# PCB_power-distribution.net
KiCad netlist of a schematic drawn in EasyEDA Pro
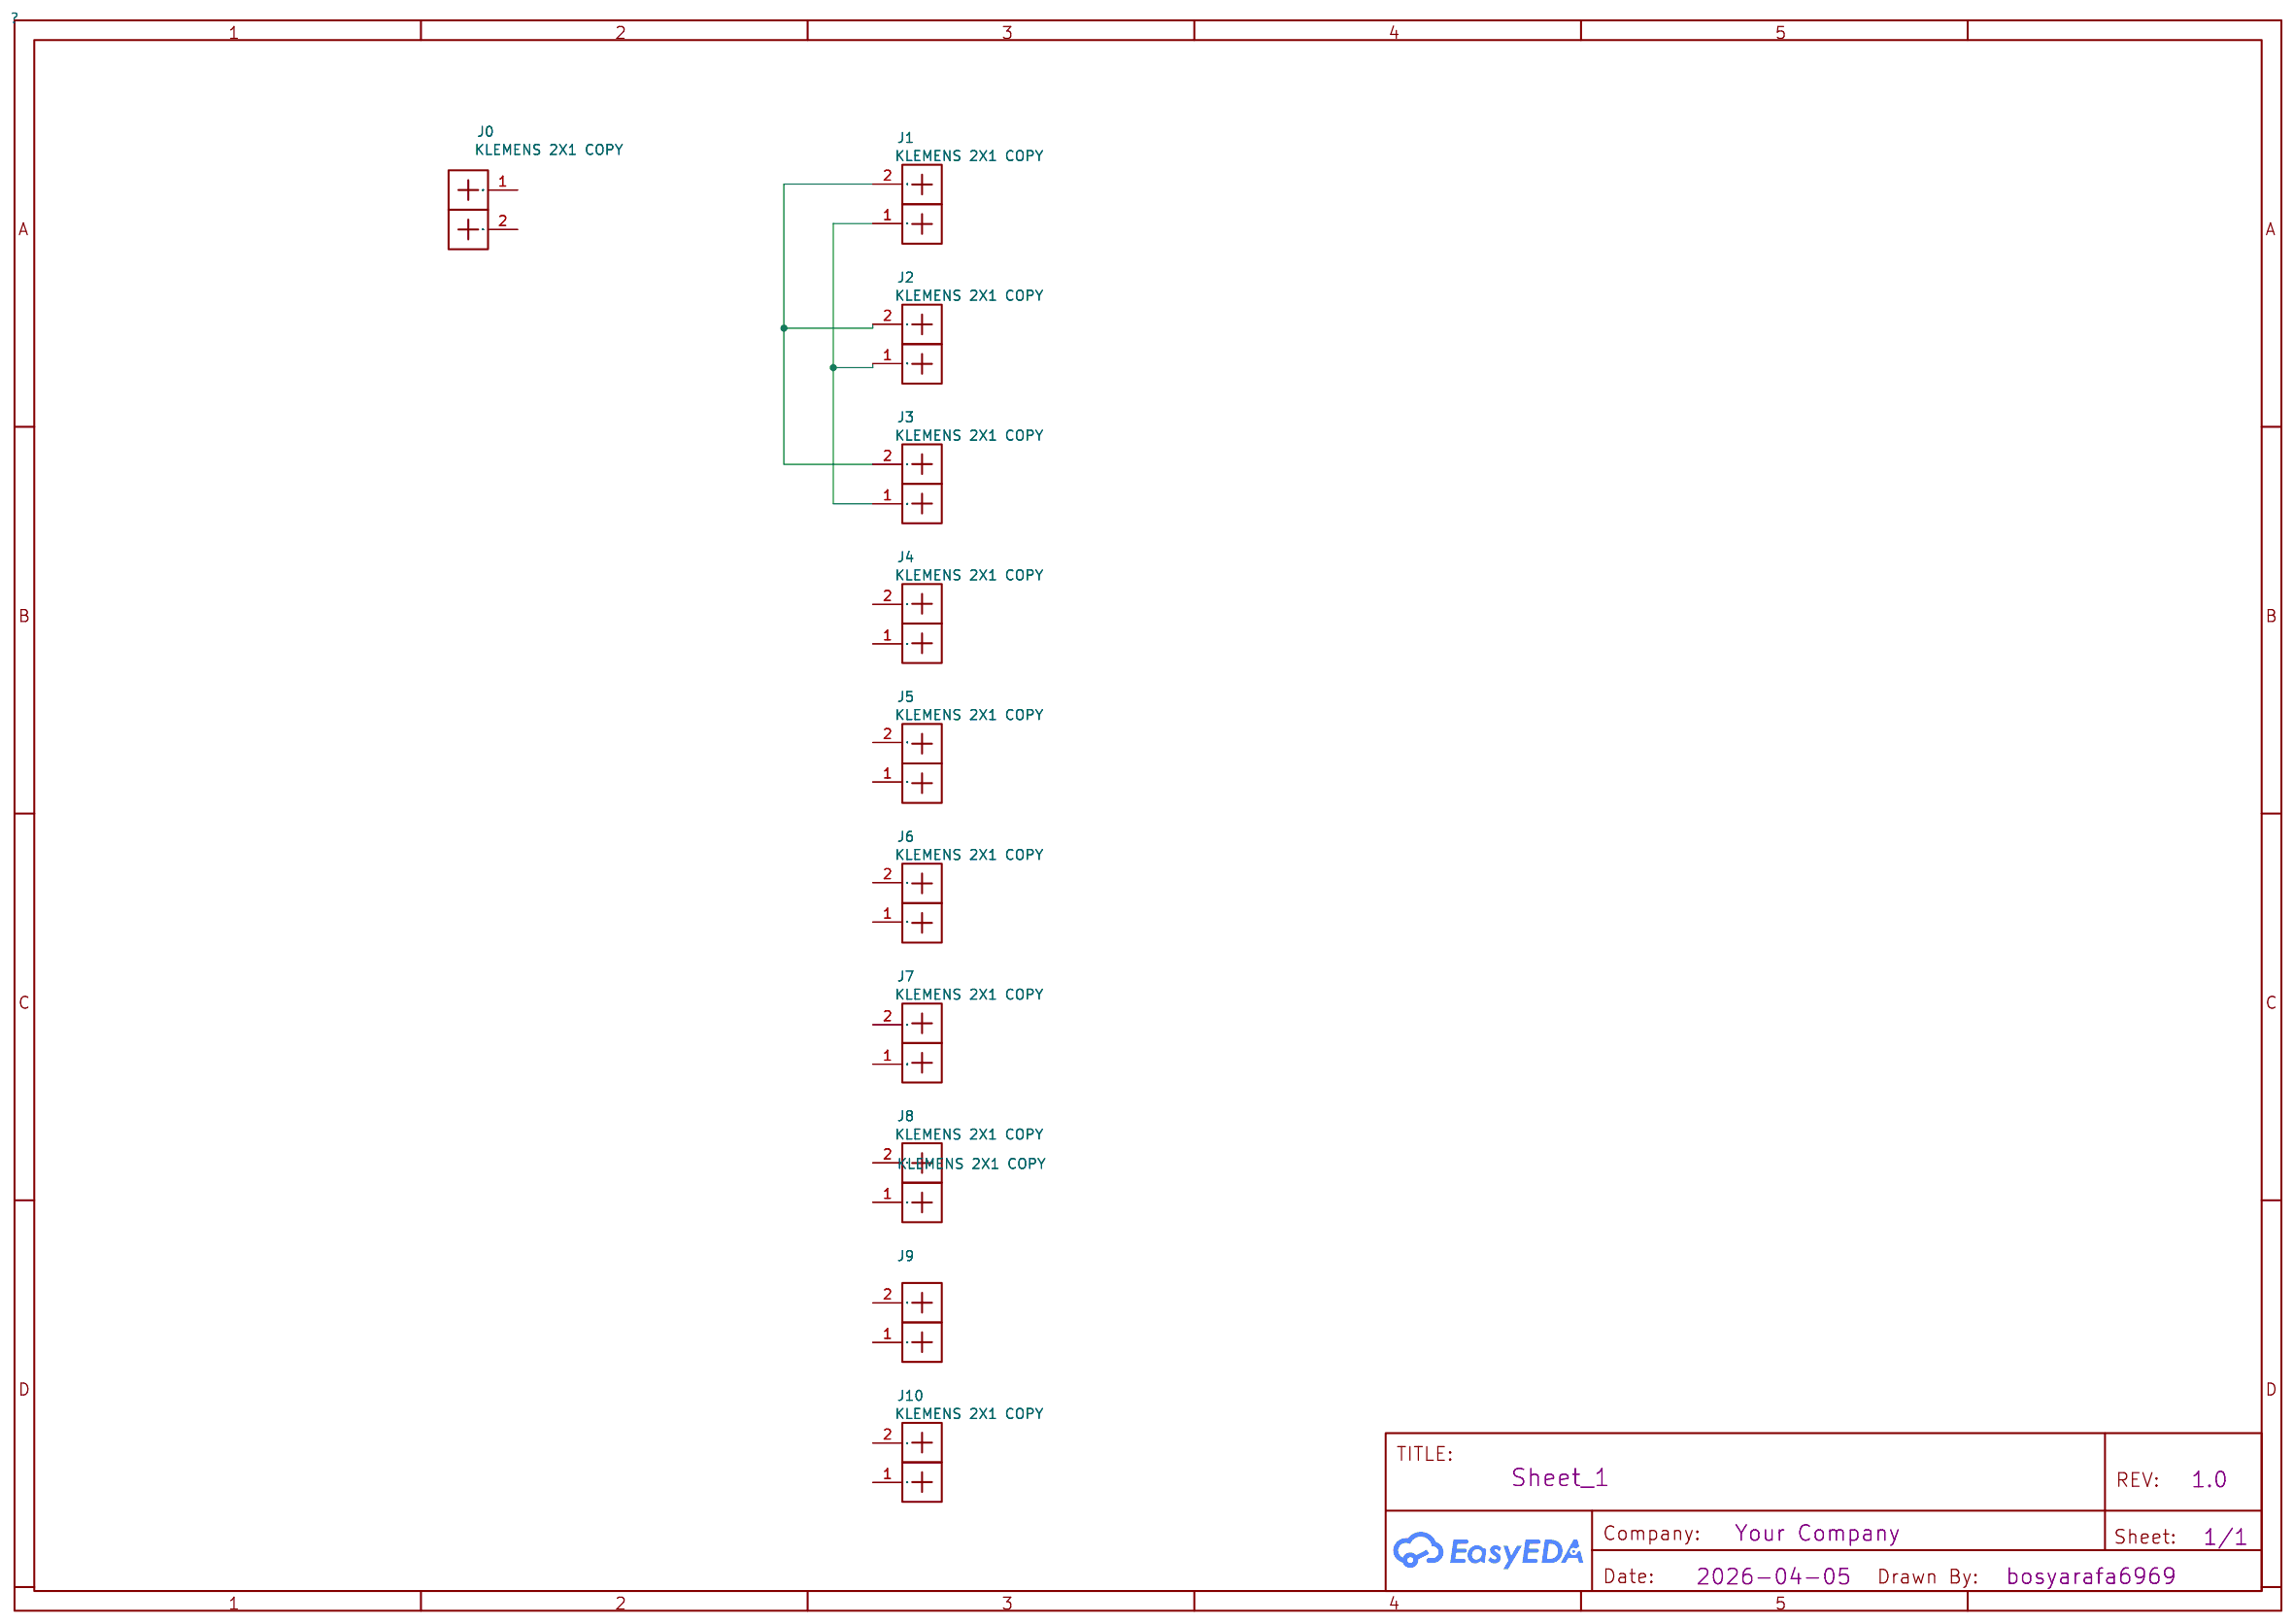
[diagram p0: schematic sheet]

(export (version "E")
  (design (tool "Eeschema 10.0.6"))
  (components
    (comp (ref "J0")
      (value "KLEMENS 2X1 COPY")
      (footprint "easyedapro:TERMINALBLOCK_METZCONNECT:TERMINALBLOCK_METZCONNECT_360271_1X01_HORIZONTAL_SCREWM3.0_BOXED")
      (fields
        (field (name "Comment") "Connector_Screw_Terminal_01x01")
        (field (name "Contributor") "fjju1212")
      )
      (libsource (lib "") (part "KLEMENS 2X1 COPY_3"))
    )
    (comp (ref "J1")
      (value "KLEMENS 2X1 COPY")
      (footprint "easyedapro:TERMINALBLOCK_METZCONNECT:TERMINALBLOCK_METZCONNECT_360271_1X01_HORIZONTAL_SCREWM3.0_BOXED")
      (fields
        (field (name "Comment") "Connector_Screw_Terminal_01x01")
        (field (name "Contributor") "fjju1212")
      )
      (libsource (lib "") (part "KLEMENS 2X1 COPY_6"))
    )
    (comp (ref "J2")
      (value "KLEMENS 2X1 COPY")
      (footprint "easyedapro:TERMINALBLOCK_METZCONNECT:TERMINALBLOCK_METZCONNECT_360271_1X01_HORIZONTAL_SCREWM3.0_BOXED")
      (fields
        (field (name "Comment") "Connector_Screw_Terminal_01x01")
        (field (name "Contributor") "fjju1212")
      )
      (libsource (lib "") (part "KLEMENS 2X1 COPY_1"))
    )
    (comp (ref "J3")
      (value "KLEMENS 2X1 COPY")
      (footprint "easyedapro:TERMINALBLOCK_METZCONNECT:TERMINALBLOCK_METZCONNECT_360271_1X01_HORIZONTAL_SCREWM3.0_BOXED")
      (fields
        (field (name "Comment") "Connector_Screw_Terminal_01x01")
        (field (name "Contributor") "fjju1212")
      )
      (libsource (lib "") (part "KLEMENS 2X1 COPY_7"))
    )
    (comp (ref "J4")
      (value "KLEMENS 2X1 COPY")
      (footprint "easyedapro:TERMINALBLOCK_METZCONNECT:TERMINALBLOCK_METZCONNECT_360271_1X01_HORIZONTAL_SCREWM3.0_BOXED")
      (fields
        (field (name "Comment") "Connector_Screw_Terminal_01x01")
        (field (name "Contributor") "fjju1212")
      )
      (libsource (lib "") (part "KLEMENS 2X1 COPY_8"))
    )
    (comp (ref "J5")
      (value "KLEMENS 2X1 COPY")
      (footprint "easyedapro:TERMINALBLOCK_METZCONNECT:TERMINALBLOCK_METZCONNECT_360271_1X01_HORIZONTAL_SCREWM3.0_BOXED")
      (fields
        (field (name "Comment") "Connector_Screw_Terminal_01x01")
        (field (name "Contributor") "fjju1212")
      )
      (libsource (lib "") (part "KLEMENS 2X1 COPY_5"))
    )
    (comp (ref "J6")
      (value "KLEMENS 2X1 COPY")
      (footprint "easyedapro:TERMINALBLOCK_METZCONNECT:TERMINALBLOCK_METZCONNECT_360271_1X01_HORIZONTAL_SCREWM3.0_BOXED")
      (fields
        (field (name "Comment") "Connector_Screw_Terminal_01x01")
        (field (name "Contributor") "fjju1212")
      )
      (libsource (lib "") (part "KLEMENS 2X1 COPY_2"))
    )
    (comp (ref "J7")
      (value "KLEMENS 2X1 COPY")
      (footprint "easyedapro:TERMINALBLOCK_METZCONNECT:TERMINALBLOCK_METZCONNECT_360271_1X01_HORIZONTAL_SCREWM3.0_BOXED")
      (fields
        (field (name "Comment") "Connector_Screw_Terminal_01x01")
        (field (name "Contributor") "fjju1212")
      )
      (libsource (lib "") (part "KLEMENS 2X1 COPY_4"))
    )
    (comp (ref "J8")
      (value "KLEMENS 2X1 COPY")
      (footprint "easyedapro:TERMINALBLOCK_METZCONNECT:TERMINALBLOCK_METZCONNECT_360271_1X01_HORIZONTAL_SCREWM3.0_BOXED")
      (fields
        (field (name "Comment") "Connector_Screw_Terminal_01x01")
        (field (name "Contributor") "fjju1212")
      )
      (libsource (lib "") (part "KLEMENS 2X1 COPY_1"))
    )
    (comp (ref "J9")
      (value "KLEMENS 2X1 COPY")
      (footprint "easyedapro:TERMINALBLOCK_METZCONNECT:TERMINALBLOCK_METZCONNECT_360271_1X01_HORIZONTAL_SCREWM3.0_BOXED")
      (fields
        (field (name "Comment") "Connector_Screw_Terminal_01x01")
        (field (name "Contributor") "fjju1212")
      )
      (libsource (lib "") (part "KLEMENS 2X1 COPY_7"))
    )
    (comp (ref "J10")
      (value "KLEMENS 2X1 COPY")
      (footprint "easyedapro:TERMINALBLOCK_METZCONNECT:TERMINALBLOCK_METZCONNECT_360271_1X01_HORIZONTAL_SCREWM3.0_BOXED")
      (fields
        (field (name "Comment") "Connector_Screw_Terminal_01x01")
        (field (name "Contributor") "fjju1212")
      )
      (libsource (lib "easyedapro") (part "KLEMENS 2X1 COPY"))
    )
  )
  (nets
    (net (code "1") (name "Net-(J1-Gnd)") (class "Default")
      (node (ref "J1") (pin "1") (pinfunction "Gnd_1") (pintype "unspecified"))
      (node (ref "J2") (pin "1") (pinfunction "Gnd_1") (pintype "unspecified"))
      (node (ref "J3") (pin "1") (pinfunction "Gnd_1") (pintype "unspecified"))
    )
    (net (code "2") (name "Net-(J1-Vcc)") (class "Default")
      (node (ref "J1") (pin "2") (pinfunction "Vcc_2") (pintype "unspecified"))
      (node (ref "J2") (pin "2") (pinfunction "Vcc_2") (pintype "unspecified"))
      (node (ref "J3") (pin "2") (pinfunction "Vcc_2") (pintype "unspecified"))
    )
    (net (code "3") (name "unconnected-(J0-Gnd-Pad1)") (class "Default")
      (node (ref "J0") (pin "1") (pinfunction "Gnd_1") (pintype "unspecified"))
    )
    (net (code "4") (name "unconnected-(J0-Vcc-Pad2)") (class "Default")
      (node (ref "J0") (pin "2") (pinfunction "Vcc_2") (pintype "unspecified"))
    )
    (net (code "5") (name "unconnected-(J4-Gnd-Pad1)") (class "Default")
      (node (ref "J4") (pin "1") (pinfunction "Gnd_1") (pintype "unspecified"))
    )
    (net (code "6") (name "unconnected-(J4-Vcc-Pad2)") (class "Default")
      (node (ref "J4") (pin "2") (pinfunction "Vcc_2") (pintype "unspecified"))
    )
    (net (code "7") (name "unconnected-(J5-Gnd-Pad1)") (class "Default")
      (node (ref "J5") (pin "1") (pinfunction "Gnd_1") (pintype "unspecified"))
    )
    (net (code "8") (name "unconnected-(J5-Vcc-Pad2)") (class "Default")
      (node (ref "J5") (pin "2") (pinfunction "Vcc_2") (pintype "unspecified"))
    )
    (net (code "9") (name "unconnected-(J6-Gnd-Pad1)") (class "Default")
      (node (ref "J6") (pin "1") (pinfunction "Gnd_1") (pintype "unspecified"))
    )
    (net (code "10") (name "unconnected-(J6-Vcc-Pad2)") (class "Default")
      (node (ref "J6") (pin "2") (pinfunction "Vcc_2") (pintype "unspecified"))
    )
    (net (code "11") (name "unconnected-(J7-Gnd-Pad1)") (class "Default")
      (node (ref "J7") (pin "1") (pinfunction "Gnd_1") (pintype "unspecified"))
    )
    (net (code "12") (name "unconnected-(J7-Vcc-Pad2)") (class "Default")
      (node (ref "J7") (pin "2") (pinfunction "Vcc_2") (pintype "unspecified"))
    )
    (net (code "13") (name "unconnected-(J8-Gnd-Pad1)") (class "Default")
      (node (ref "J8") (pin "1") (pinfunction "Gnd_1") (pintype "unspecified"))
    )
    (net (code "14") (name "unconnected-(J8-Vcc-Pad2)") (class "Default")
      (node (ref "J8") (pin "2") (pinfunction "Vcc_2") (pintype "unspecified"))
    )
    (net (code "15") (name "unconnected-(J9-Gnd-Pad1)") (class "Default")
      (node (ref "J9") (pin "1") (pinfunction "Gnd_1") (pintype "unspecified"))
    )
    (net (code "16") (name "unconnected-(J9-Vcc-Pad2)") (class "Default")
      (node (ref "J9") (pin "2") (pinfunction "Vcc_2") (pintype "unspecified"))
    )
    (net (code "17") (name "unconnected-(J10-Gnd-Pad1)") (class "Default")
      (node (ref "J10") (pin "1") (pinfunction "Gnd_1") (pintype "unspecified"))
    )
    (net (code "18") (name "unconnected-(J10-Vcc-Pad2)") (class "Default")
      (node (ref "J10") (pin "2") (pinfunction "Vcc_2") (pintype "unspecified"))
    )
  )
)
